# Main.net
KiCad netlist of a schematic drawn in Altium Designer
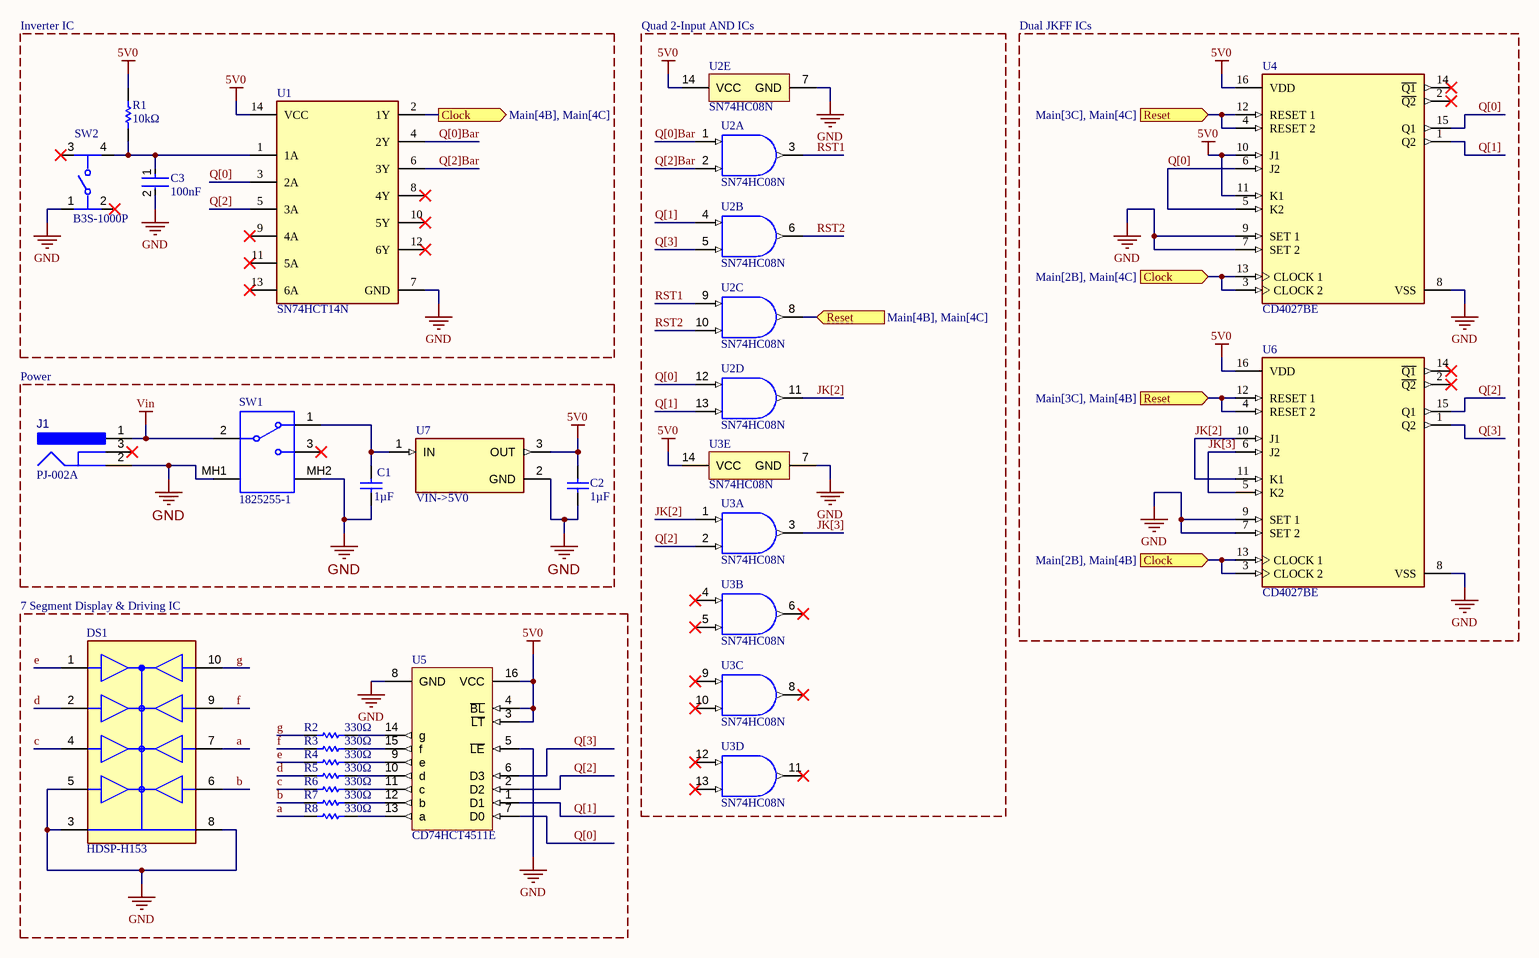
[diagram p0: Main.SchDoc]

(export (version "E")
  (design (tool "Eeschema 10.0.6"))
  (components
    (comp (ref "C1")
      (value "1µF")
      (footprint "CAPC3216X110X50LL20T25")
      (description "Chip Capacitor, 1 uF, +/- 10%, 50 V, -55 to 125 degC, 1206 (3216 Metric), RoHS, Tape and Reel")
      (fields (field (name "MANUFACTURER") "Kemet") (field (name "TOLERANCE") "10%"))
      (libsource (lib "Altium Content Vault") (part "CAP-NP-2"))
    )
    (comp (ref "C2")
      (value "1µF")
      (footprint "CAPC3216X110X50LL20T25")
      (description "Chip Capacitor, 1 uF, +/- 10%, 50 V, -55 to 125 degC, 1206 (3216 Metric), RoHS, Tape and Reel")
      (fields (field (name "MANUFACTURER") "Kemet") (field (name "TOLERANCE") "10%"))
      (libsource (lib "Altium Content Vault") (part "CAP-NP-2"))
    )
    (comp (ref "C3")
      (value "100nF")
      (footprint "FP-C1206C-EB-MFG")
      (description "CAP CER 0.1UF 200V 10% X7R 1206")
      (fields (field (name "TOLERANCE") "0.1") (field (name "MANUFACTURER PART NUMBER") "C1206C104K2RACTU"))
      (libsource (lib "Altium Content Vault") (part "b4654b650e69147ec39a6b967a45e02"))
    )
    (comp (ref "DS1")
      (value "HDSP-H153")
      (footprint "FP-HDSP-H153-MFG")
      (description "LED 7-SEG 14.2MM CC RED RHD RHD")
      (fields
        (field (name "OCTOPART") "https://octopart.com/hdsp-h153-broadcom-71129578")
        (field (name "MANUFACTURER") "Broadcom")
      )
      (libsource (lib "Altium Content Vault") (part "84a80ac4071a6eb1a0df8b92a28a5e0"))
    )
    (comp (ref "J1")
      (value "PJ-002A")
      (footprint "CUI-PJ-002A_V")
      (fields (field (name "MANUFACTURER") "CUIInc."))
      (libsource (lib "Altium Content Vault") (part "JACK-2CD3-RN_B"))
    )
    (comp (ref "R1")
      (value "10kΩ")
      (footprint "RESC3116X65X40ML10T20")
      (description "Chip Resistor, 10 KOhm, +/- 1%, 0.25 W, -55 to 155 degC, 1206 (3216 Metric), RoHS, Tape and Reel")
      (fields (field (name "TOLERANCE") "1%") (field (name "MANUFACTURER") "Yageo"))
      (libsource (lib "Altium Content Vault") (part "RES-2"))
    )
    (comp (ref "R2")
      (value "330Ω")
      (footprint "RESC3216X70X50NL05T20")
      (fields (field (name "PART NUMBER") "ERJ8ENF3300V") (field (name "MANUFACTURER") "Panasonic"))
      (libsource (lib "Altium Content Vault") (part "RES"))
    )
    (comp (ref "R3")
      (value "330Ω")
      (footprint "RESC3216X70X50NL05T20")
      (fields (field (name "PART NUMBER") "ERJ8ENF3300V") (field (name "MANUFACTURER") "Panasonic"))
      (libsource (lib "Altium Content Vault") (part "RES"))
    )
    (comp (ref "R4")
      (value "330Ω")
      (footprint "RESC3216X70X50NL05T20")
      (fields (field (name "PART NUMBER") "ERJ8ENF3300V") (field (name "MANUFACTURER") "Panasonic"))
      (libsource (lib "Altium Content Vault") (part "RES"))
    )
    (comp (ref "R5")
      (value "330Ω")
      (footprint "RESC3216X70X50NL05T20")
      (fields (field (name "PART NUMBER") "ERJ8ENF3300V") (field (name "MANUFACTURER") "Panasonic"))
      (libsource (lib "Altium Content Vault") (part "RES"))
    )
    (comp (ref "R6")
      (value "330Ω")
      (footprint "RESC3216X70X50NL05T20")
      (fields (field (name "PART NUMBER") "ERJ8ENF3300V") (field (name "MANUFACTURER") "Panasonic"))
      (libsource (lib "Altium Content Vault") (part "RES"))
    )
    (comp (ref "R7")
      (value "330Ω")
      (footprint "RESC3216X70X50NL05T20")
      (fields (field (name "PART NUMBER") "ERJ8ENF3300V") (field (name "MANUFACTURER") "Panasonic"))
      (libsource (lib "Altium Content Vault") (part "RES"))
    )
    (comp (ref "R8")
      (value "330Ω")
      (footprint "RESC3216X70X50NL05T20")
      (fields (field (name "PART NUMBER") "ERJ8ENF3300V") (field (name "MANUFACTURER") "Panasonic"))
      (libsource (lib "Altium Content Vault") (part "RES"))
    )
    (comp (ref "SW1")
      (value "1825255-1")
      (footprint "TECO-1825255-1_V")
      (description "Slide Switch, SPDT, 125 V, -20 to 85 degC, 5-Pin THD, RoHS, Tray")
      (fields (field (name "MANUFACTURER") "TE Connectivity"))
      (libsource (lib "Altium Content Vault") (part "SW-SPDT-3_C"))
    )
    (comp (ref "SW2")
      (value "B3S-1000P")
      (footprint "FP-B3S-1000P-MFG")
      (description "SWITCH TACTILE SPST-NO 0.05A 24V")
      (libsource (lib "Altium Content Vault") (part "b8895f3f4cefb76e1819d2863dba89b"))
    )
    (comp (ref "U1")
      (value "SN74HCT14N")
      (footprint "FP-N0014A-MFG")
      (description "IC INVERTER SCHMITT 6CH 14DIP")
      (libsource (lib "Altium Content Vault") (part "1835e6eef6524eafa27badc82040dd5"))
    )
    (comp (ref "U2")
      (value "SN74HC08N")
      (footprint "N0014A")
      (description "Quadruple 2-Input Positive-AND Gates, N0014A, TUBE")
      (fields
        (field (name "GENERIC PART NUMBER") "SN74HC08")
        (field (name "MANUFACTURER") "Texas Instruments")
      )
      (libsource (lib "Altium Content Vault") (part "TI-AND-4-2IN-14"))
    )
    (comp (ref "U3")
      (value "SN74HC08N")
      (footprint "N0014A")
      (description "Quadruple 2-Input Positive-AND Gates, N0014A, TUBE")
      (fields
        (field (name "GENERIC PART NUMBER") "SN74HC08")
        (field (name "MANUFACTURER") "Texas Instruments")
      )
      (libsource (lib "Altium Content Vault") (part "TI-AND-4-2IN-14"))
    )
    (comp (ref "U4")
      (value "CD4027BE")
      (footprint "FP-N0016A-MFG")
      (description "IC FF JK TYPE DUAL 1BIT 16DIP")
      (libsource (lib "Altium Content Vault") (part "d291e76beeaa4d512229545176fb353"))
    )
    (comp (ref "U5")
      (value "CD74HCT4511E")
      (footprint "N0016A")
      (fields (field (name "MANUFACTURER") "Texas Instruments"))
      (libsource (lib "Altium Content Vault") (part "TI-CD54_74HCX4511-16"))
    )
    (comp (ref "U6")
      (value "CD4027BE")
      (footprint "FP-N0016A-MFG")
      (description "IC FF JK TYPE DUAL 1BIT 16DIP")
      (libsource (lib "Altium Content Vault") (part "d291e76beeaa4d512229545176fb353"))
    )
    (comp (ref "U7")
      (value "VIN->5V0")
      (footprint "DPAK229P990X238-4N")
      (description "Linear Voltage Regulator IC 1 Output 1A DPAK")
      (fields (field (name "MP") "MC7805BDTRKG") (field (name "MF") "ON Semiconductor"))
      (libsource (lib "MC7805BDTRKG") (part "MC7805BDTRKG"))
    )
  )
  (nets
    (net (code "1") (name "/Clock") (class "Default")
      (node (ref "U1") (pin "2") (pinfunction "1Y_2") (pintype "passive"))
      (node (ref "U4") (pin "13") (pinfunction "CLOCK_1_13") (pintype "input"))
      (node (ref "U4") (pin "3") (pinfunction "CLOCK_2_3") (pintype "input"))
      (node (ref "U6") (pin "13") (pinfunction "CLOCK_1_13") (pintype "input"))
      (node (ref "U6") (pin "3") (pinfunction "CLOCK_2_3") (pintype "input"))
    )
    (net (code "2") (name "/JK[2]") (class "Default")
      (node (ref "U2") (pin "11") (pinfunction "4Y_11") (pintype "output"))
      (node (ref "U3") (pin "1") (pinfunction "1A_1") (pintype "input"))
      (node (ref "U6") (pin "10") (pinfunction "J1_10") (pintype "input"))
      (node (ref "U6") (pin "11") (pinfunction "K1_11") (pintype "input"))
    )
    (net (code "3") (name "/JK[3]") (class "Default")
      (node (ref "U3") (pin "3") (pinfunction "1Y_3") (pintype "output"))
      (node (ref "U6") (pin "5") (pinfunction "K2_5") (pintype "input"))
      (node (ref "U6") (pin "6") (pinfunction "J2_6") (pintype "input"))
    )
    (net (code "4") (name "/Q[0]") (class "Default")
      (node (ref "U1") (pin "3") (pinfunction "2A_3") (pintype "passive"))
      (node (ref "U2") (pin "12") (pinfunction "4A_12") (pintype "input"))
      (node (ref "U4") (pin "15") (pinfunction "Q1_15") (pintype "output"))
      (node (ref "U4") (pin "5") (pinfunction "K2_5") (pintype "input"))
      (node (ref "U4") (pin "6") (pinfunction "J2_6") (pintype "input"))
      (node (ref "U5") (pin "7") (pinfunction "D0_7") (pintype "input"))
    )
    (net (code "5") (name "/Q[0]Bar") (class "Default")
      (node (ref "U1") (pin "4") (pinfunction "2Y_4") (pintype "passive"))
      (node (ref "U2") (pin "1") (pinfunction "1A_1") (pintype "input"))
    )
    (net (code "6") (name "/Q[1]") (class "Default")
      (node (ref "U2") (pin "13") (pinfunction "4B_13") (pintype "input"))
      (node (ref "U2") (pin "4") (pinfunction "2A_4") (pintype "input"))
      (node (ref "U4") (pin "1") (pinfunction "Q2_1") (pintype "output"))
      (node (ref "U5") (pin "1") (pinfunction "D1_1") (pintype "input"))
    )
    (net (code "7") (name "/Q[2]") (class "Default")
      (node (ref "U1") (pin "5") (pinfunction "3A_5") (pintype "passive"))
      (node (ref "U3") (pin "2") (pinfunction "1B_2") (pintype "input"))
      (node (ref "U5") (pin "2") (pinfunction "D2_2") (pintype "input"))
      (node (ref "U6") (pin "15") (pinfunction "Q1_15") (pintype "output"))
    )
    (net (code "8") (name "/Q[2]Bar") (class "Default")
      (node (ref "U1") (pin "6") (pinfunction "3Y_6") (pintype "passive"))
      (node (ref "U2") (pin "2") (pinfunction "1B_2") (pintype "input"))
    )
    (net (code "9") (name "/Q[3]") (class "Default")
      (node (ref "U2") (pin "5") (pinfunction "2B_5") (pintype "input"))
      (node (ref "U5") (pin "6") (pinfunction "D3_6") (pintype "input"))
      (node (ref "U6") (pin "1") (pinfunction "Q2_1") (pintype "output"))
    )
    (net (code "10") (name "/RST1") (class "Default")
      (node (ref "U2") (pin "3") (pinfunction "1Y_3") (pintype "output"))
      (node (ref "U2") (pin "9") (pinfunction "3A_9") (pintype "input"))
    )
    (net (code "11") (name "/RST2") (class "Default")
      (node (ref "U2") (pin "10") (pinfunction "3B_10") (pintype "input"))
      (node (ref "U2") (pin "6") (pinfunction "2Y_6") (pintype "output"))
    )
    (net (code "12") (name "/Reset") (class "Default")
      (node (ref "U2") (pin "8") (pinfunction "3Y_8") (pintype "output"))
      (node (ref "U4") (pin "12") (pinfunction "RESET_1_12") (pintype "input"))
      (node (ref "U4") (pin "4") (pinfunction "RESET_2_4") (pintype "input"))
      (node (ref "U6") (pin "12") (pinfunction "RESET_1_12") (pintype "input"))
      (node (ref "U6") (pin "4") (pinfunction "RESET_2_4") (pintype "input"))
    )
    (net (code "13") (name "/a") (class "Default")
      (node (ref "DS1") (pin "7") (pinfunction "ANODE_a_7") (pintype "passive"))
      (node (ref "R8") (pin "1") (pinfunction "1_1") (pintype "passive"))
    )
    (net (code "14") (name "/b") (class "Default")
      (node (ref "DS1") (pin "6") (pinfunction "ANODE_b_6") (pintype "passive"))
      (node (ref "R7") (pin "1") (pinfunction "1_1") (pintype "passive"))
    )
    (net (code "15") (name "/c") (class "Default")
      (node (ref "DS1") (pin "4") (pinfunction "ANODE_c_4") (pintype "passive"))
      (node (ref "R6") (pin "1") (pinfunction "1_1") (pintype "passive"))
    )
    (net (code "16") (name "/d") (class "Default")
      (node (ref "DS1") (pin "2") (pinfunction "ANODE_d_2") (pintype "passive"))
      (node (ref "R5") (pin "1") (pinfunction "1_1") (pintype "passive"))
    )
    (net (code "17") (name "/e") (class "Default")
      (node (ref "DS1") (pin "1") (pinfunction "ANODE_e_1") (pintype "passive"))
      (node (ref "R4") (pin "1") (pinfunction "1_1") (pintype "passive"))
    )
    (net (code "18") (name "/f") (class "Default")
      (node (ref "DS1") (pin "9") (pinfunction "ANODE_f_9") (pintype "passive"))
      (node (ref "R3") (pin "1") (pinfunction "1_1") (pintype "passive"))
    )
    (net (code "19") (name "/g") (class "Default")
      (node (ref "DS1") (pin "10") (pinfunction "ANODE_g_10") (pintype "passive"))
      (node (ref "R2") (pin "1") (pinfunction "1_1") (pintype "passive"))
    )
    (net (code "20") (name "5V0") (class "Default")
      (node (ref "C2") (pin "1") (pinfunction "1_1") (pintype "passive"))
      (node (ref "R1") (pin "2") (pinfunction "2_2") (pintype "passive"))
      (node (ref "U1") (pin "14") (pinfunction "VCC_14") (pintype "passive"))
      (node (ref "U2") (pin "14") (pinfunction "VCC_14") (pintype "power_in"))
      (node (ref "U3") (pin "14") (pinfunction "VCC_14") (pintype "power_in"))
      (node (ref "U4") (pin "10") (pinfunction "J1_10") (pintype "input"))
      (node (ref "U4") (pin "11") (pinfunction "K1_11") (pintype "input"))
      (node (ref "U4") (pin "16") (pinfunction "VDD_16") (pintype "power_in"))
      (node (ref "U5") (pin "16") (pinfunction "VCC_16") (pintype "power_in"))
      (node (ref "U5") (pin "3") (pinfunction "~{LT}_3") (pintype "input"))
      (node (ref "U5") (pin "4") (pinfunction "~{BL}_4") (pintype "input"))
      (node (ref "U6") (pin "16") (pinfunction "VDD_16") (pintype "power_in"))
      (node (ref "U7") (pin "3") (pinfunction "OUT_3") (pintype "output"))
    )
    (net (code "21") (name "GND") (class "Default")
      (node (ref "C1") (pin "2") (pinfunction "2_2") (pintype "passive"))
      (node (ref "C2") (pin "2") (pinfunction "2_2") (pintype "passive"))
      (node (ref "C3") (pin "2") (pinfunction "2_2") (pintype "passive"))
      (node (ref "DS1") (pin "3") (pinfunction "C_3") (pintype "passive"))
      (node (ref "DS1") (pin "5") (pinfunction "ANODE_DP_5") (pintype "passive"))
      (node (ref "DS1") (pin "8") (pinfunction "C_8") (pintype "passive"))
      (node (ref "J1") (pin "2") (pinfunction "2_2") (pintype "passive"))
      (node (ref "SW1") (pin "MH1") (pinfunction "MH1_MH1") (pintype "passive"))
      (node (ref "SW1") (pin "MH2") (pinfunction "MH2_MH2") (pintype "passive"))
      (node (ref "SW2") (pin "1") (pinfunction "1_1") (pintype "passive"))
      (node (ref "U1") (pin "7") (pinfunction "GND_7") (pintype "passive"))
      (node (ref "U2") (pin "7") (pinfunction "GND_7") (pintype "power_in"))
      (node (ref "U3") (pin "7") (pinfunction "GND_7") (pintype "power_in"))
      (node (ref "U4") (pin "7") (pinfunction "SET_2_7") (pintype "input"))
      (node (ref "U4") (pin "8") (pinfunction "VSS_8") (pintype "power_in"))
      (node (ref "U4") (pin "9") (pinfunction "SET_1_9") (pintype "input"))
      (node (ref "U5") (pin "5") (pinfunction "~{LE}_5") (pintype "input"))
      (node (ref "U5") (pin "8") (pinfunction "GND_8") (pintype "power_in"))
      (node (ref "U6") (pin "7") (pinfunction "SET_2_7") (pintype "input"))
      (node (ref "U6") (pin "8") (pinfunction "VSS_8") (pintype "power_in"))
      (node (ref "U6") (pin "9") (pinfunction "SET_1_9") (pintype "input"))
      (node (ref "U7") (pin "2") (pinfunction "GND_2") (pintype "power_in"))
    )
    (net (code "22") (name "Net-(U1-1A)") (class "Default")
      (node (ref "C3") (pin "1") (pinfunction "1_1") (pintype "passive"))
      (node (ref "R1") (pin "1") (pinfunction "1_1") (pintype "passive"))
      (node (ref "SW2") (pin "4") (pinfunction "4_4") (pintype "passive"))
      (node (ref "U1") (pin "1") (pinfunction "1A_1") (pintype "passive"))
    )
    (net (code "23") (name "Net-(U5-a)") (class "Default")
      (node (ref "R8") (pin "2") (pinfunction "2_2") (pintype "passive"))
      (node (ref "U5") (pin "13") (pinfunction "a_13") (pintype "output"))
    )
    (net (code "24") (name "Net-(U5-b)") (class "Default")
      (node (ref "R7") (pin "2") (pinfunction "2_2") (pintype "passive"))
      (node (ref "U5") (pin "12") (pinfunction "b_12") (pintype "output"))
    )
    (net (code "25") (name "Net-(U5-c)") (class "Default")
      (node (ref "R6") (pin "2") (pinfunction "2_2") (pintype "passive"))
      (node (ref "U5") (pin "11") (pinfunction "c_11") (pintype "output"))
    )
    (net (code "26") (name "Net-(U5-d)") (class "Default")
      (node (ref "R5") (pin "2") (pinfunction "2_2") (pintype "passive"))
      (node (ref "U5") (pin "10") (pinfunction "d_10") (pintype "output"))
    )
    (net (code "27") (name "Net-(U5-e)") (class "Default")
      (node (ref "R4") (pin "2") (pinfunction "2_2") (pintype "passive"))
      (node (ref "U5") (pin "9") (pinfunction "e_9") (pintype "output"))
    )
    (net (code "28") (name "Net-(U5-f)") (class "Default")
      (node (ref "R3") (pin "2") (pinfunction "2_2") (pintype "passive"))
      (node (ref "U5") (pin "15") (pinfunction "f_15") (pintype "output"))
    )
    (net (code "29") (name "Net-(U5-g)") (class "Default")
      (node (ref "R2") (pin "2") (pinfunction "2_2") (pintype "passive"))
      (node (ref "U5") (pin "14") (pinfunction "g_14") (pintype "output"))
    )
    (net (code "30") (name "Net-(U7-IN)") (class "Default")
      (node (ref "C1") (pin "1") (pinfunction "1_1") (pintype "passive"))
      (node (ref "SW1") (pin "1") (pinfunction "1_1") (pintype "passive"))
      (node (ref "U7") (pin "1") (pinfunction "IN_1") (pintype "input"))
    )
    (net (code "31") (name "Vin") (class "Default")
      (node (ref "J1") (pin "1") (pinfunction "1_1") (pintype "passive"))
      (node (ref "SW1") (pin "2") (pinfunction "2_2") (pintype "passive"))
    )
    (net (code "32") (name "unconnected-(J1-Pad3)") (class "Default")
      (node (ref "J1") (pin "3") (pinfunction "3_3") (pintype "passive+no_connect"))
    )
    (net (code "33") (name "unconnected-(SW1-Pad3)") (class "Default")
      (node (ref "SW1") (pin "3") (pinfunction "3_3") (pintype "passive+no_connect"))
    )
    (net (code "34") (name "unconnected-(SW2-Pad2)") (class "Default")
      (node (ref "SW2") (pin "2") (pinfunction "2_2") (pintype "passive+no_connect"))
    )
    (net (code "35") (name "unconnected-(SW2-Pad3)") (class "Default")
      (node (ref "SW2") (pin "3") (pinfunction "3_3") (pintype "passive+no_connect"))
    )
    (net (code "36") (name "unconnected-(U1-4A-Pad9)") (class "Default")
      (node (ref "U1") (pin "9") (pinfunction "4A_9") (pintype "passive+no_connect"))
    )
    (net (code "37") (name "unconnected-(U1-4Y-Pad8)") (class "Default")
      (node (ref "U1") (pin "8") (pinfunction "4Y_8") (pintype "passive+no_connect"))
    )
    (net (code "38") (name "unconnected-(U1-5A-Pad11)") (class "Default")
      (node (ref "U1") (pin "11") (pinfunction "5A_11") (pintype "passive+no_connect"))
    )
    (net (code "39") (name "unconnected-(U1-5Y-Pad10)") (class "Default")
      (node (ref "U1") (pin "10") (pinfunction "5Y_10") (pintype "passive+no_connect"))
    )
    (net (code "40") (name "unconnected-(U1-6A-Pad13)") (class "Default")
      (node (ref "U1") (pin "13") (pinfunction "6A_13") (pintype "passive+no_connect"))
    )
    (net (code "41") (name "unconnected-(U1-6Y-Pad12)") (class "Default")
      (node (ref "U1") (pin "12") (pinfunction "6Y_12") (pintype "passive+no_connect"))
    )
    (net (code "42") (name "unconnected-(U3B-2A-Pad4)") (class "Default")
      (node (ref "U3") (pin "4") (pinfunction "2A_4") (pintype "input+no_connect"))
    )
    (net (code "43") (name "unconnected-(U3B-2B-Pad5)") (class "Default")
      (node (ref "U3") (pin "5") (pinfunction "2B_5") (pintype "input+no_connect"))
    )
    (net (code "44") (name "unconnected-(U3B-2Y-Pad6)") (class "Default")
      (node (ref "U3") (pin "6") (pinfunction "2Y_6") (pintype "output+no_connect"))
    )
    (net (code "45") (name "unconnected-(U3C-3A-Pad9)") (class "Default")
      (node (ref "U3") (pin "9") (pinfunction "3A_9") (pintype "input+no_connect"))
    )
    (net (code "46") (name "unconnected-(U3C-3B-Pad10)") (class "Default")
      (node (ref "U3") (pin "10") (pinfunction "3B_10") (pintype "input+no_connect"))
    )
    (net (code "47") (name "unconnected-(U3C-3Y-Pad8)") (class "Default")
      (node (ref "U3") (pin "8") (pinfunction "3Y_8") (pintype "output+no_connect"))
    )
    (net (code "48") (name "unconnected-(U3D-4A-Pad12)") (class "Default")
      (node (ref "U3") (pin "12") (pinfunction "4A_12") (pintype "input+no_connect"))
    )
    (net (code "49") (name "unconnected-(U3D-4B-Pad13)") (class "Default")
      (node (ref "U3") (pin "13") (pinfunction "4B_13") (pintype "input+no_connect"))
    )
    (net (code "50") (name "unconnected-(U3D-4Y-Pad11)") (class "Default")
      (node (ref "U3") (pin "11") (pinfunction "4Y_11") (pintype "output+no_connect"))
    )
    (net (code "51") (name "unconnected-(U4-~{Q1}-Pad14)") (class "Default")
      (node (ref "U4") (pin "14") (pinfunction "~{Q1}_14") (pintype "output+no_connect"))
    )
    (net (code "52") (name "unconnected-(U4-~{Q2}-Pad2)") (class "Default")
      (node (ref "U4") (pin "2") (pinfunction "~{Q2}_2") (pintype "output+no_connect"))
    )
    (net (code "53") (name "unconnected-(U6-~{Q1}-Pad14)") (class "Default")
      (node (ref "U6") (pin "14") (pinfunction "~{Q1}_14") (pintype "output+no_connect"))
    )
    (net (code "54") (name "unconnected-(U6-~{Q2}-Pad2)") (class "Default")
      (node (ref "U6") (pin "2") (pinfunction "~{Q2}_2") (pintype "output+no_connect"))
    )
  )
)
